# RS232-RS485-PC.net
KiCad netlist of a schematic drawn in Altium Designer
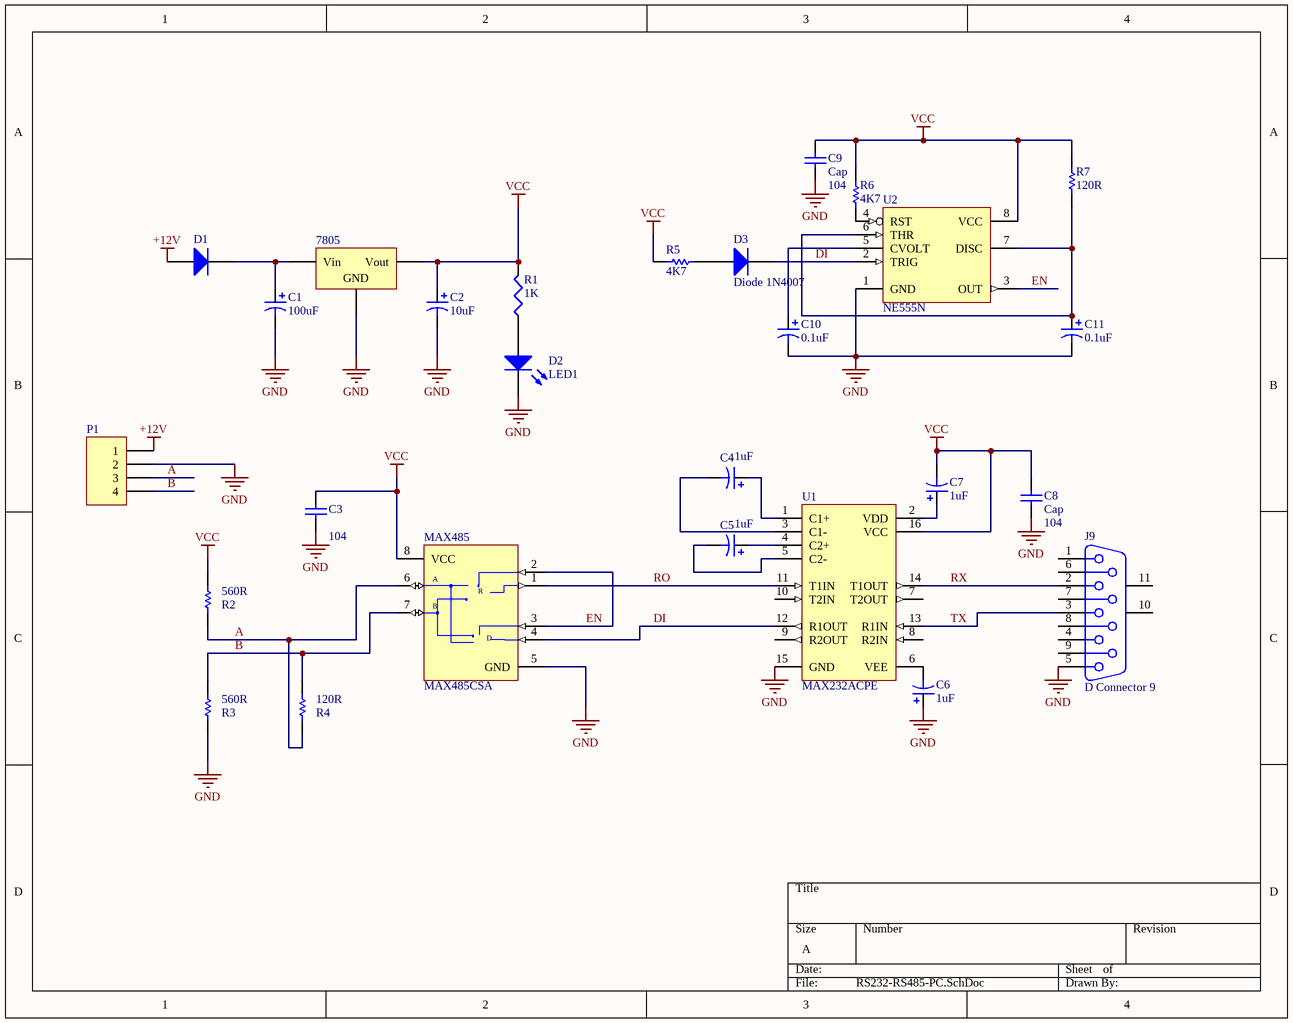
[diagram p0: RS232-RS485-PC.SchDoc]

(export (version "E")
  (design (tool "Eeschema 10.0.6"))
  (components
    (comp (ref "7805")
      (value "Volt Reg")
      (footprint "Device:78xx_NO")
      (description "Voltage Regulator")
      (fields (field (name "PUBLISHER") "Altium Limited"))
      (libsource (lib "Miscellaneous Devices") (part "Volt Reg"))
    )
    (comp (ref "C1")
      (value "100uF")
      (footprint "Device:tu 100uF/50v")
      (description "Polarized Capacitor (Radial)")
      (fields (field (name "Comment") "Cap Pol1") (field (name "PUBLISHER") "Altium Limited"))
      (libsource (lib "Miscellaneous Devices") (part "Cap Pol1"))
    )
    (comp (ref "C2")
      (value "10uF")
      (footprint "Device:tu 10uF")
      (description "Polarized Capacitor (Radial)")
      (fields (field (name "Comment") "Cap Pol1") (field (name "PUBLISHER") "Altium Limited"))
      (libsource (lib "Miscellaneous Devices") (part "Cap Pol1"))
    )
    (comp (ref "C3")
      (value "104")
      (footprint "Device:C104_YELLOW")
      (description "Capcitor")
      (fields (field (name "Comment") "Cap"))
      (libsource (lib "Device_Component") (part "Ceramic"))
    )
    (comp (ref "C4")
      (value "1uF")
      (footprint "Device:tu 10uF")
      (description "Polarized Capacitor (Radial)")
      (fields (field (name "Comment") "Cap Pol1") (field (name "PUBLISHER") "Altium Limited"))
      (libsource (lib "Miscellaneous Devices") (part "Cap Pol1"))
    )
    (comp (ref "C5")
      (value "1uF")
      (footprint "Device:tu 10uF")
      (description "Polarized Capacitor (Radial)")
      (fields (field (name "Comment") "Cap Pol1") (field (name "PUBLISHER") "Altium Limited"))
      (libsource (lib "Miscellaneous Devices") (part "Cap Pol1"))
    )
    (comp (ref "C6")
      (value "1uF")
      (footprint "Device:tu 10uF")
      (description "Polarized Capacitor (Radial)")
      (fields (field (name "Comment") "Cap Pol1") (field (name "PUBLISHER") "Altium Limited"))
      (libsource (lib "Miscellaneous Devices") (part "Cap Pol1"))
    )
    (comp (ref "C7")
      (value "1uF")
      (footprint "Device:tu 10uF")
      (description "Polarized Capacitor (Radial)")
      (fields (field (name "Comment") "Cap Pol1") (field (name "PUBLISHER") "Altium Limited"))
      (libsource (lib "Miscellaneous Devices") (part "Cap Pol1"))
    )
    (comp (ref "C8")
      (value "Cap")
      (footprint "Device:C104_YELLOW")
      (description "Capcitor")
      (fields (field (name "ALTIUM_VALUE") "104"))
      (libsource (lib "Device_Component") (part "Ceramic"))
    )
    (comp (ref "C9")
      (value "Cap")
      (footprint "Device:C104_YELLOW")
      (description "Capcitor")
      (fields (field (name "ALTIUM_VALUE") "104"))
      (libsource (lib "Device_Component") (part "Ceramic"))
    )
    (comp (ref "C10")
      (value "0.1uF")
      (footprint "Device:C104_YELLOW")
      (description "Polarized Capacitor (Radial)")
      (fields (field (name "Comment") "Cap Pol1") (field (name "PUBLISHER") "Altium Limited"))
      (libsource (lib "Miscellaneous Devices") (part "Cap Pol1"))
    )
    (comp (ref "C11")
      (value "0.1uF")
      (footprint "Device:C104_YELLOW")
      (description "Polarized Capacitor (Radial)")
      (fields (field (name "Comment") "Cap Pol1") (field (name "PUBLISHER") "Altium Limited"))
      (libsource (lib "Miscellaneous Devices") (part "Cap Pol1"))
    )
    (comp (ref "D1")
      (value "Diode 1N4007")
      (footprint "Device:D_2A")
      (description "1 Amp General Purpose Rectifier")
      (fields (field (name "PUBLISHER") "Altium Limited"))
      (libsource (lib "Miscellaneous Devices") (part "Diode 1N4007"))
    )
    (comp (ref "D2")
      (value "LED1")
      (footprint "Device:LED_3")
      (description "Typical RED GaAs LED")
      (fields (field (name "PUBLISHER") "Altium Limited"))
      (libsource (lib "Miscellaneous Devices") (part "LED1"))
    )
    (comp (ref "D3")
      (value "Diode 1N4007")
      (footprint "Device:D_1A")
      (description "1 Amp General Purpose Rectifier")
      (fields (field (name "PUBLISHER") "Altium Limited"))
      (libsource (lib "Miscellaneous Devices") (part "Diode 1N4007"))
    )
    (comp (ref "J9")
      (value "D Connector 9")
      (footprint "Device:COM9_2")
      (description "Receptacle Assembly, 9 Position, Right Angle")
      (fields (field (name "PUBLISHER") "Altium Limited"))
      (libsource (lib "Miscellaneous Connectors") (part "D Connector 9"))
    )
    (comp (ref "MAX485")
      (value "MAX485CSA")
      (footprint "Maxim Footprints:PA8")
      (description "Low-Power, Slew-Rate-Limited RS-485/RS-422 Transceiver")
      (fields (field (name "PUBLISHER") "Altium Limited"))
      (libsource (lib "Maxim Communication Transceiver") (part "MAX485CSA"))
    )
    (comp (ref "P1")
      (value "Header 4")
      (footprint "Device:Header4")
      (description "Header, 4-Pin")
      (fields (field (name "PUBLISHER") "Altium Limited"))
      (libsource (lib "Miscellaneous Connectors") (part "Header 4"))
    )
    (comp (ref "R1")
      (value "1K")
      (footprint "Device:R_Nor")
      (description "Resistor")
      (fields (field (name "Comment") "Res3") (field (name "PUBLISHER") "Altium Limited"))
      (libsource (lib "Miscellaneous Devices") (part "Res3"))
    )
    (comp (ref "R2")
      (value "560R")
      (footprint "Device:R_Nor")
      (libsource (lib "Device_Component") (part "Res"))
    )
    (comp (ref "R3")
      (value "560R")
      (footprint "Device:R_Nor")
      (libsource (lib "Device_Component") (part "Res"))
    )
    (comp (ref "R4")
      (value "120R")
      (footprint "Device:R_Nor")
      (libsource (lib "Device_Component") (part "Res"))
    )
    (comp (ref "R5")
      (value "4K7")
      (footprint "Device:R_Nor")
      (libsource (lib "Device_Component") (part "Res"))
    )
    (comp (ref "R6")
      (value "4K7")
      (footprint "Device:R_Nor")
      (libsource (lib "Device_Component") (part "Res"))
    )
    (comp (ref "R7")
      (value "120R")
      (footprint "Device:R_Nor")
      (libsource (lib "Device_Component") (part "Res"))
    )
    (comp (ref "U1")
      (value "MAX232ACPE")
      (footprint "Maxim Footprints:PE16A")
      (description "+5V Powered, Multi-Channel RS-232 Driver/Receiver")
      (fields (field (name "PUBLISHER") "Altium Limited"))
      (libsource (lib "Maxim Communication Transceiver") (part "MAX232ACPE"))
    )
    (comp (ref "U2")
      (value "NE555N")
      (footprint "DIP8")
      (description "General-Purpose Single Bipolar Timer")
      (fields (field (name "PUBLISHER") "Altium Limited"))
      (libsource (lib "ST Analog Timer Circuit") (part "NE555N"))
    )
  )
  (nets
    (net (code "1") (name "+12V") (class "Default")
      (node (ref "D1") (pin "1") (pinfunction "A_1") (pintype "passive"))
      (node (ref "P1") (pin "1") (pinfunction "1_1") (pintype "passive"))
    )
    (net (code "2") (name "/A") (class "Default")
      (node (ref "MAX485") (pin "6") (pinfunction "A_6") (pintype "bidirectional"))
      (node (ref "P1") (pin "3") (pinfunction "3_3") (pintype "passive"))
      (node (ref "R2") (pin "1") (pinfunction "1_1") (pintype "passive"))
      (node (ref "R4") (pin "1") (pinfunction "1_1") (pintype "passive"))
    )
    (net (code "3") (name "/B") (class "Default")
      (node (ref "MAX485") (pin "7") (pinfunction "B_7") (pintype "bidirectional"))
      (node (ref "P1") (pin "4") (pinfunction "4_4") (pintype "passive"))
      (node (ref "R3") (pin "2") (pinfunction "2_2") (pintype "passive"))
      (node (ref "R4") (pin "2") (pinfunction "2_2") (pintype "passive"))
    )
    (net (code "4") (name "/DI") (class "Default")
      (node (ref "D3") (pin "2") (pinfunction "K_2") (pintype "passive"))
      (node (ref "MAX485") (pin "4") (pinfunction "DI_4") (pintype "input"))
      (node (ref "U1") (pin "12") (pinfunction "R1OUT_12") (pintype "output"))
      (node (ref "U2") (pin "2") (pinfunction "TRIG_2") (pintype "input"))
    )
    (net (code "5") (name "/EN") (class "Default")
      (node (ref "MAX485") (pin "2") (pinfunction "~{RE}_2") (pintype "input"))
      (node (ref "MAX485") (pin "3") (pinfunction "DE_3") (pintype "input"))
      (node (ref "U2") (pin "3") (pinfunction "OUT_3") (pintype "output"))
    )
    (net (code "6") (name "/RO") (class "Default")
      (node (ref "MAX485") (pin "1") (pinfunction "RO_1") (pintype "output"))
      (node (ref "U1") (pin "11") (pinfunction "T1IN_11") (pintype "input"))
    )
    (net (code "7") (name "/RX") (class "Default")
      (node (ref "J9") (pin "2") (pinfunction "2_2") (pintype "passive"))
      (node (ref "U1") (pin "14") (pinfunction "T1OUT_14") (pintype "output"))
    )
    (net (code "8") (name "/TX") (class "Default")
      (node (ref "J9") (pin "3") (pinfunction "3_3") (pintype "passive"))
      (node (ref "U1") (pin "13") (pinfunction "R1IN_13") (pintype "input"))
    )
    (net (code "9") (name "GND") (class "Default")
      (node (ref "7805") (pin "2") (pinfunction "GND_2") (pintype "passive"))
      (node (ref "C1") (pin "2") (pinfunction "2_2") (pintype "passive"))
      (node (ref "C10") (pin "2") (pinfunction "2_2") (pintype "passive"))
      (node (ref "C11") (pin "2") (pinfunction "2_2") (pintype "passive"))
      (node (ref "C2") (pin "2") (pinfunction "2_2") (pintype "passive"))
      (node (ref "C3") (pin "1") (pinfunction "1_1") (pintype "passive"))
      (node (ref "C6") (pin "1") (pinfunction "1_1") (pintype "passive"))
      (node (ref "C8") (pin "1") (pinfunction "1_1") (pintype "passive"))
      (node (ref "C9") (pin "1") (pinfunction "1_1") (pintype "passive"))
      (node (ref "D2") (pin "2") (pinfunction "K_2") (pintype "passive"))
      (node (ref "J9") (pin "5") (pinfunction "5_5") (pintype "passive"))
      (node (ref "MAX485") (pin "5") (pinfunction "GND_5") (pintype "power_in"))
      (node (ref "P1") (pin "2") (pinfunction "2_2") (pintype "passive"))
      (node (ref "R3") (pin "1") (pinfunction "1_1") (pintype "passive"))
      (node (ref "U1") (pin "15") (pinfunction "GND_15") (pintype "power_in"))
      (node (ref "U2") (pin "1") (pinfunction "GND_1") (pintype "power_in"))
    )
    (net (code "10") (name "Net-(7805-Vin)") (class "Default")
      (node (ref "7805") (pin "1") (pinfunction "Vin_1") (pintype "passive"))
      (node (ref "C1") (pin "1") (pinfunction "1_1") (pintype "passive"))
      (node (ref "D1") (pin "2") (pinfunction "K_2") (pintype "passive"))
    )
    (net (code "11") (name "Net-(D2-A)") (class "Default")
      (node (ref "D2") (pin "1") (pinfunction "A_1") (pintype "passive"))
      (node (ref "R1") (pin "1") (pinfunction "1_1") (pintype "passive"))
    )
    (net (code "12") (name "Net-(D3-A)") (class "Default")
      (node (ref "D3") (pin "1") (pinfunction "A_1") (pintype "passive"))
      (node (ref "R5") (pin "1") (pinfunction "1_1") (pintype "passive"))
    )
    (net (code "13") (name "Net-(U1-C1+)") (class "Default")
      (node (ref "C4") (pin "1") (pinfunction "1_1") (pintype "passive"))
      (node (ref "U1") (pin "1") (pinfunction "C1+_1") (pintype "passive"))
    )
    (net (code "14") (name "Net-(U1-C1-)") (class "Default")
      (node (ref "C4") (pin "2") (pinfunction "2_2") (pintype "passive"))
      (node (ref "U1") (pin "3") (pinfunction "C1-_3") (pintype "passive"))
    )
    (net (code "15") (name "Net-(U1-C2+)") (class "Default")
      (node (ref "C5") (pin "1") (pinfunction "1_1") (pintype "passive"))
      (node (ref "U1") (pin "4") (pinfunction "C2+_4") (pintype "passive"))
    )
    (net (code "16") (name "Net-(U1-C2-)") (class "Default")
      (node (ref "C5") (pin "2") (pinfunction "2_2") (pintype "passive"))
      (node (ref "U1") (pin "5") (pinfunction "C2-_5") (pintype "passive"))
    )
    (net (code "17") (name "Net-(U1-VDD)") (class "Default")
      (node (ref "C7") (pin "1") (pinfunction "1_1") (pintype "passive"))
      (node (ref "U1") (pin "2") (pinfunction "VDD_2") (pintype "power_in"))
    )
    (net (code "18") (name "Net-(U1-VEE)") (class "Default")
      (node (ref "C6") (pin "2") (pinfunction "2_2") (pintype "passive"))
      (node (ref "U1") (pin "6") (pinfunction "VEE_6") (pintype "power_in"))
    )
    (net (code "19") (name "Net-(U2-CVOLT)") (class "Default")
      (node (ref "C10") (pin "1") (pinfunction "1_1") (pintype "passive"))
      (node (ref "U2") (pin "5") (pinfunction "CVOLT_5") (pintype "passive"))
    )
    (net (code "20") (name "Net-(U2-DISC)") (class "Default")
      (node (ref "C11") (pin "1") (pinfunction "1_1") (pintype "passive"))
      (node (ref "R7") (pin "2") (pinfunction "2_2") (pintype "passive"))
      (node (ref "U2") (pin "6") (pinfunction "THR_6") (pintype "input"))
      (node (ref "U2") (pin "7") (pinfunction "DISC_7") (pintype "open_collector"))
    )
    (net (code "21") (name "Net-(U2-RST)") (class "Default")
      (node (ref "R6") (pin "2") (pinfunction "2_2") (pintype "passive"))
      (node (ref "U2") (pin "4") (pinfunction "RST_4") (pintype "input"))
    )
    (net (code "22") (name "VCC") (class "Default")
      (node (ref "7805") (pin "3") (pinfunction "Vout_3") (pintype "passive"))
      (node (ref "C2") (pin "1") (pinfunction "1_1") (pintype "passive"))
      (node (ref "C3") (pin "2") (pinfunction "2_2") (pintype "passive"))
      (node (ref "C7") (pin "2") (pinfunction "2_2") (pintype "passive"))
      (node (ref "C8") (pin "2") (pinfunction "2_2") (pintype "passive"))
      (node (ref "C9") (pin "2") (pinfunction "2_2") (pintype "passive"))
      (node (ref "MAX485") (pin "8") (pinfunction "VCC_8") (pintype "power_in"))
      (node (ref "R1") (pin "2") (pinfunction "2_2") (pintype "passive"))
      (node (ref "R2") (pin "2") (pinfunction "2_2") (pintype "passive"))
      (node (ref "R5") (pin "2") (pinfunction "2_2") (pintype "passive"))
      (node (ref "R6") (pin "1") (pinfunction "1_1") (pintype "passive"))
      (node (ref "R7") (pin "1") (pinfunction "1_1") (pintype "passive"))
      (node (ref "U1") (pin "16") (pinfunction "VCC_16") (pintype "power_in"))
      (node (ref "U2") (pin "8") (pinfunction "VCC_8") (pintype "power_in"))
    )
    (net (code "23") (name "unconnected-(J9-MH1-Pad10)") (class "Default")
      (node (ref "J9") (pin "10") (pinfunction "MH1_10") (pintype "passive"))
    )
    (net (code "24") (name "unconnected-(J9-MH2-Pad11)") (class "Default")
      (node (ref "J9") (pin "11") (pinfunction "MH2_11") (pintype "passive"))
    )
    (net (code "25") (name "unconnected-(J9-Pad1)") (class "Default")
      (node (ref "J9") (pin "1") (pinfunction "1_1") (pintype "passive"))
    )
    (net (code "26") (name "unconnected-(J9-Pad4)") (class "Default")
      (node (ref "J9") (pin "4") (pinfunction "4_4") (pintype "passive"))
    )
    (net (code "27") (name "unconnected-(J9-Pad6)") (class "Default")
      (node (ref "J9") (pin "6") (pinfunction "6_6") (pintype "passive"))
    )
    (net (code "28") (name "unconnected-(J9-Pad7)") (class "Default")
      (node (ref "J9") (pin "7") (pinfunction "7_7") (pintype "passive"))
    )
    (net (code "29") (name "unconnected-(J9-Pad8)") (class "Default")
      (node (ref "J9") (pin "8") (pinfunction "8_8") (pintype "passive"))
    )
    (net (code "30") (name "unconnected-(J9-Pad9)") (class "Default")
      (node (ref "J9") (pin "9") (pinfunction "9_9") (pintype "passive"))
    )
    (net (code "31") (name "unconnected-(U1-R2IN-Pad8)") (class "Default")
      (node (ref "U1") (pin "8") (pinfunction "R2IN_8") (pintype "input"))
    )
    (net (code "32") (name "unconnected-(U1-R2OUT-Pad9)") (class "Default")
      (node (ref "U1") (pin "9") (pinfunction "R2OUT_9") (pintype "output"))
    )
    (net (code "33") (name "unconnected-(U1-T2IN-Pad10)") (class "Default")
      (node (ref "U1") (pin "10") (pinfunction "T2IN_10") (pintype "input"))
    )
    (net (code "34") (name "unconnected-(U1-T2OUT-Pad7)") (class "Default")
      (node (ref "U1") (pin "7") (pinfunction "T2OUT_7") (pintype "output"))
    )
  )
)
